# STM32F103RCT6_Core.net
KiCad netlist of a schematic drawn in Altium Designer
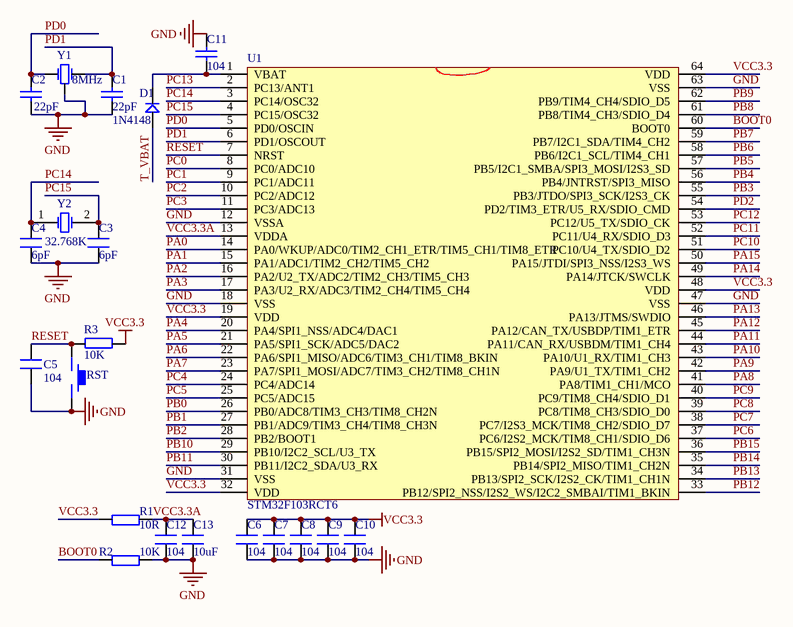
[diagram p0: STM32F103RCT6_Core.SchDoc]

(export (version "E")
  (design (tool "Eeschema 10.0.6"))
  (components
    (comp (ref "C1") (value "22pF") (footprint "C 0603_M") (libsource (lib "L476") (part "CAP")))
    (comp (ref "C2") (value "22pF") (footprint "C 0603_M") (libsource (lib "L476") (part "CAP")))
    (comp (ref "C3")
      (value "6pF")
      (footprint "C 0603_M")
      (libsource (lib "WarShip V3 STM32103封装库") (part "C"))
    )
    (comp (ref "C4")
      (value "6pF")
      (footprint "C 0603_M")
      (libsource (lib "WarShip V3 STM32103封装库") (part "C"))
    )
    (comp (ref "C5")
      (value "104")
      (footprint "C 0603_M")
      (libsource (lib "WarShip V3 STM32103封装库") (part "C"))
    )
    (comp (ref "C6")
      (value "104")
      (footprint "C 0603_M")
      (libsource (lib "WarShip V3 STM32103封装库") (part "C"))
    )
    (comp (ref "C7")
      (value "104")
      (footprint "C 0603_M")
      (libsource (lib "WarShip V3 STM32103封装库") (part "C"))
    )
    (comp (ref "C8")
      (value "104")
      (footprint "C 0603_M")
      (libsource (lib "WarShip V3 STM32103封装库") (part "C"))
    )
    (comp (ref "C9")
      (value "104")
      (footprint "C 0603_M")
      (libsource (lib "WarShip V3 STM32103封装库") (part "C"))
    )
    (comp (ref "C10")
      (value "104")
      (footprint "C 0603_M")
      (libsource (lib "WarShip V3 STM32103封装库") (part "C"))
    )
    (comp (ref "C11") (value "104") (footprint "C 0603_M") (libsource (lib "L476") (part "CAP")))
    (comp (ref "C12")
      (value "104")
      (footprint "C 0603_M")
      (libsource (lib "WarShip V3 STM32103封装库") (part "C"))
    )
    (comp (ref "C13")
      (value "10uF")
      (footprint "C 0603_M")
      (libsource (lib "WarShip V3 STM32103封装库") (part "C"))
    )
    (comp (ref "D1")
      (value "1N4148")
      (footprint "MINI_MELF (LL34)")
      (libsource (lib "阿波罗STM32F4&F7底板封装库") (part "D"))
    )
    (comp (ref "R1")
      (value "10R")
      (footprint "R 0603_M")
      (libsource (lib "WarShip V3 STM32103封装库") (part "R"))
    )
    (comp (ref "R2")
      (value "10K")
      (footprint "R 0603_M")
      (libsource (lib "WarShip V3 STM32103封装库") (part "R"))
    )
    (comp (ref "R3")
      (value "10K")
      (footprint "R 0603_M")
      (libsource (lib "WarShip V3 STM32103封装库") (part "R"))
    )
    (comp (ref "RST")
      (value "S-KEY-SMD-324225")
      (footprint "TSW SMD-3*6*2.5")
      (description "KEY,SMD,324225")
      (libsource (lib "Pandora_STM32L4_Board_V2.4") (part "S-KEY-SMD-324225"))
    )
    (comp (ref "U1")
      (value "STM32F103RCT6")
      (footprint "LQFP-64N")
      (libsource (lib "MiniSTM32 V3.0封装库") (part "STM32F103RDT6"))
    )
    (comp (ref "Y1")
      (value "8MHz")
      (footprint "Y-XTAL-3215-3P")
      (description "XTAL,3215,8MHz")
      (libsource (lib "Pandora_STM32L4_Board_V2.4") (part "Y-3215-8M"))
    )
    (comp (ref "Y2")
      (value "32.768K")
      (footprint "OSC 3215-2P")
      (description "Crystal Oscillator")
      (fields (field (name "PUBLISHER") "Altium Limited"))
      (libsource (lib "WarShip V3 STM32103封装库") (part "XTAL"))
    )
  )
  (nets
    (net (code "1") (name "/BOOT0") (class "Default")
      (node (ref "R2") (pin "1") (pintype "passive"))
      (node (ref "U1") (pin "60") (pinfunction "BOOT0_60") (pintype "passive"))
    )
    (net (code "2") (name "/PA0") (class "Default")
      (node (ref "U1") (pin "14") (pinfunction "PA0/WKUP/ADC0/TIM2_CH1_ETR/TIM5_CH1/TIM8_ETR_14") (pintype "passive"))
    )
    (net (code "3") (name "/PA1") (class "Default")
      (node (ref "U1") (pin "15") (pinfunction "PA1/ADC1/TIM2_CH2/TIM5_CH2_15") (pintype "passive"))
    )
    (net (code "4") (name "/PA2") (class "Default")
      (node (ref "U1") (pin "16") (pinfunction "PA2/U2_TX/ADC2/TIM2_CH3/TIM5_CH3_16") (pintype "passive"))
    )
    (net (code "5") (name "/PA3") (class "Default")
      (node (ref "U1") (pin "17") (pinfunction "PA3/U2_RX/ADC3/TIM2_CH4/TIM5_CH4_17") (pintype "passive"))
    )
    (net (code "6") (name "/PA4") (class "Default")
      (node (ref "U1") (pin "20") (pinfunction "PA4/SPI1_NSS/ADC4/DAC1_20") (pintype "passive"))
    )
    (net (code "7") (name "/PA5") (class "Default")
      (node (ref "U1") (pin "21") (pinfunction "PA5/SPI1_SCK/ADC5/DAC2_21") (pintype "passive"))
    )
    (net (code "8") (name "/PA6") (class "Default")
      (node (ref "U1") (pin "22") (pinfunction "PA6/SPI1_MISO/ADC6/TIM3_CH1/TIM8_BKIN_22") (pintype "passive"))
    )
    (net (code "9") (name "/PA7") (class "Default")
      (node (ref "U1") (pin "23") (pinfunction "PA7/SPI1_MOSI/ADC7/TIM3_CH2/TIM8_CH1N_23") (pintype "passive"))
    )
    (net (code "10") (name "/PA8") (class "Default")
      (node (ref "U1") (pin "41") (pinfunction "PA8/TIM1_CH1/MCO_41") (pintype "passive"))
    )
    (net (code "11") (name "/PA9") (class "Default")
      (node (ref "U1") (pin "42") (pinfunction "PA9/U1_TX/TIM1_CH2_42") (pintype "passive"))
    )
    (net (code "12") (name "/PA10") (class "Default")
      (node (ref "U1") (pin "43") (pinfunction "PA10/U1_RX/TIM1_CH3_43") (pintype "passive"))
    )
    (net (code "13") (name "/PA11") (class "Default")
      (node (ref "U1") (pin "44") (pinfunction "PA11/CAN_RX/USBDM/TIM1_CH4_44") (pintype "passive"))
    )
    (net (code "14") (name "/PA12") (class "Default")
      (node (ref "U1") (pin "45") (pinfunction "PA12/CAN_TX/USBDP/TIM1_ETR_45") (pintype "passive"))
    )
    (net (code "15") (name "/PA13") (class "Default")
      (node (ref "U1") (pin "46") (pinfunction "PA13/JTMS/SWDIO_46") (pintype "passive"))
    )
    (net (code "16") (name "/PA14") (class "Default")
      (node (ref "U1") (pin "49") (pinfunction "PA14/JTCK/SWCLK_49") (pintype "passive"))
    )
    (net (code "17") (name "/PA15") (class "Default")
      (node (ref "U1") (pin "50") (pinfunction "PA15/JTDI/SPI3_NSS/I2S3_WS_50") (pintype "passive"))
    )
    (net (code "18") (name "/PB0") (class "Default")
      (node (ref "U1") (pin "26") (pinfunction "PB0/ADC8/TIM3_CH3/TIM8_CH2N_26") (pintype "passive"))
    )
    (net (code "19") (name "/PB1") (class "Default")
      (node (ref "U1") (pin "27") (pinfunction "PB1/ADC9/TIM3_CH4/TIM8_CH3N_27") (pintype "passive"))
    )
    (net (code "20") (name "/PB2") (class "Default")
      (node (ref "U1") (pin "28") (pinfunction "PB2/BOOT1_28") (pintype "passive"))
    )
    (net (code "21") (name "/PB3") (class "Default")
      (node (ref "U1") (pin "55") (pinfunction "PB3/JTDO/SPI3_SCK/I2S3_CK_55") (pintype "passive"))
    )
    (net (code "22") (name "/PB4") (class "Default")
      (node (ref "U1") (pin "56") (pinfunction "PB4/JNTRST/SPI3_MISO_56") (pintype "passive"))
    )
    (net (code "23") (name "/PB5") (class "Default")
      (node (ref "U1") (pin "57") (pinfunction "PB5/I2C1_SMBA/SPI3_MOSI/I2S3_SD_57") (pintype "passive"))
    )
    (net (code "24") (name "/PB6") (class "Default")
      (node (ref "U1") (pin "58") (pinfunction "PB6/I2C1_SCL/TIM4_CH1_58") (pintype "passive"))
    )
    (net (code "25") (name "/PB7") (class "Default")
      (node (ref "U1") (pin "59") (pinfunction "PB7/I2C1_SDA/TIM4_CH2_59") (pintype "passive"))
    )
    (net (code "26") (name "/PB8") (class "Default")
      (node (ref "U1") (pin "61") (pinfunction "PB8/TIM4_CH3/SDIO_D4_61") (pintype "passive"))
    )
    (net (code "27") (name "/PB9") (class "Default")
      (node (ref "U1") (pin "62") (pinfunction "PB9/TIM4_CH4/SDIO_D5_62") (pintype "passive"))
    )
    (net (code "28") (name "/PB10") (class "Default")
      (node (ref "U1") (pin "29") (pinfunction "PB10/I2C2_SCL/U3_TX_29") (pintype "passive"))
    )
    (net (code "29") (name "/PB11") (class "Default")
      (node (ref "U1") (pin "30") (pinfunction "PB11/I2C2_SDA/U3_RX_30") (pintype "passive"))
    )
    (net (code "30") (name "/PB12") (class "Default")
      (node (ref "U1") (pin "33") (pinfunction "PB12/SPI2_NSS/I2S2_WS/I2C2_SMBAI/TIM1_BKIN_33") (pintype "passive"))
    )
    (net (code "31") (name "/PB13") (class "Default")
      (node (ref "U1") (pin "34") (pinfunction "PB13/SPI2_SCK/I2S2_CK/TIM1_CH1N_34") (pintype "passive"))
    )
    (net (code "32") (name "/PB14") (class "Default")
      (node (ref "U1") (pin "35") (pinfunction "PB14/SPI2_MISO/TIM1_CH2N_35") (pintype "passive"))
    )
    (net (code "33") (name "/PB15") (class "Default")
      (node (ref "U1") (pin "36") (pinfunction "PB15/SPI2_MOSI/I2S2_SD/TIM1_CH3N_36") (pintype "passive"))
    )
    (net (code "34") (name "/PC0") (class "Default")
      (node (ref "U1") (pin "8") (pinfunction "PC0/ADC10_8") (pintype "passive"))
    )
    (net (code "35") (name "/PC1") (class "Default")
      (node (ref "U1") (pin "9") (pinfunction "PC1/ADC11_9") (pintype "passive"))
    )
    (net (code "36") (name "/PC2") (class "Default")
      (node (ref "U1") (pin "10") (pinfunction "PC2/ADC12_10") (pintype "passive"))
    )
    (net (code "37") (name "/PC3") (class "Default")
      (node (ref "U1") (pin "11") (pinfunction "PC3/ADC13_11") (pintype "passive"))
    )
    (net (code "38") (name "/PC4") (class "Default")
      (node (ref "U1") (pin "24") (pinfunction "PC4/ADC14_24") (pintype "passive"))
    )
    (net (code "39") (name "/PC5") (class "Default")
      (node (ref "U1") (pin "25") (pinfunction "PC5/ADC15_25") (pintype "passive"))
    )
    (net (code "40") (name "/PC6") (class "Default")
      (node (ref "U1") (pin "37") (pinfunction "PC6/I2S2_MCK/TIM8_CH1/SDIO_D6_37") (pintype "passive"))
    )
    (net (code "41") (name "/PC7") (class "Default")
      (node (ref "U1") (pin "38") (pinfunction "PC7/I2S3_MCK/TIM8_CH2/SDIO_D7_38") (pintype "passive"))
    )
    (net (code "42") (name "/PC8") (class "Default")
      (node (ref "U1") (pin "39") (pinfunction "PC8/TIM8_CH3/SDIO_D0_39") (pintype "passive"))
    )
    (net (code "43") (name "/PC9") (class "Default")
      (node (ref "U1") (pin "40") (pinfunction "PC9/TIM8_CH4/SDIO_D1_40") (pintype "passive"))
    )
    (net (code "44") (name "/PC10") (class "Default")
      (node (ref "U1") (pin "51") (pinfunction "PC10/U4_TX/SDIO_D2_51") (pintype "passive"))
    )
    (net (code "45") (name "/PC11") (class "Default")
      (node (ref "U1") (pin "52") (pinfunction "PC11/U4_RX/SDIO_D3_52") (pintype "passive"))
    )
    (net (code "46") (name "/PC12") (class "Default")
      (node (ref "U1") (pin "53") (pinfunction "PC12/U5_TX/SDIO_CK_53") (pintype "passive"))
    )
    (net (code "47") (name "/PC13") (class "Default")
      (node (ref "U1") (pin "2") (pinfunction "PC13/ANT1_2") (pintype "passive"))
    )
    (net (code "48") (name "/PC14") (class "Default")
      (node (ref "C4") (pin "2") (pintype "passive"))
      (node (ref "U1") (pin "3") (pinfunction "PC14/OSC32_3") (pintype "passive"))
      (node (ref "Y2") (pin "1") (pinfunction "OSC1_1") (pintype "passive"))
    )
    (net (code "49") (name "/PC15") (class "Default")
      (node (ref "C3") (pin "2") (pintype "passive"))
      (node (ref "U1") (pin "4") (pinfunction "PC15/OSC32_4") (pintype "passive"))
      (node (ref "Y2") (pin "2") (pinfunction "OSC2_2") (pintype "passive"))
    )
    (net (code "50") (name "/PD0") (class "Default")
      (node (ref "C2") (pin "2") (pinfunction "2_2") (pintype "passive"))
      (node (ref "U1") (pin "5") (pinfunction "PD0/OSCIN_5") (pintype "passive"))
      (node (ref "Y1") (pin "1") (pinfunction "OSC1_1") (pintype "passive"))
    )
    (net (code "51") (name "/PD1") (class "Default")
      (node (ref "C1") (pin "2") (pinfunction "2_2") (pintype "passive"))
      (node (ref "U1") (pin "6") (pinfunction "PD1/OSCOUT_6") (pintype "passive"))
      (node (ref "Y1") (pin "3") (pinfunction "OSC2_3") (pintype "passive"))
    )
    (net (code "52") (name "/PD2") (class "Default")
      (node (ref "U1") (pin "54") (pinfunction "PD2/TIM3_ETR/U5_RX/SDIO_CMD_54") (pintype "passive"))
    )
    (net (code "53") (name "/RESET") (class "Default")
      (node (ref "C5") (pin "2") (pintype "passive"))
      (node (ref "R3") (pin "2") (pintype "passive"))
      (node (ref "RST") (pin "1") (pinfunction "1_1") (pintype "passive"))
      (node (ref "U1") (pin "7") (pinfunction "NRST_7") (pintype "passive"))
    )
    (net (code "54") (name "/T_VBAT") (class "Default") (node (ref "D1") (pin "1") (pintype "passive")))
    (net (code "55") (name "/VCC3.3A") (class "Default")
      (node (ref "C12") (pin "2") (pintype "passive"))
      (node (ref "C13") (pin "2") (pintype "passive"))
      (node (ref "R1") (pin "2") (pintype "passive"))
      (node (ref "U1") (pin "13") (pinfunction "VDDA_13") (pintype "passive"))
    )
    (net (code "56") (name "GND") (class "Default")
      (node (ref "C1") (pin "1") (pinfunction "1_1") (pintype "passive"))
      (node (ref "C10") (pin "1") (pintype "passive"))
      (node (ref "C11") (pin "1") (pinfunction "1_1") (pintype "passive"))
      (node (ref "C12") (pin "1") (pintype "passive"))
      (node (ref "C13") (pin "1") (pintype "passive"))
      (node (ref "C2") (pin "1") (pinfunction "1_1") (pintype "passive"))
      (node (ref "C3") (pin "1") (pintype "passive"))
      (node (ref "C4") (pin "1") (pintype "passive"))
      (node (ref "C5") (pin "1") (pintype "passive"))
      (node (ref "C6") (pin "1") (pintype "passive"))
      (node (ref "C7") (pin "1") (pintype "passive"))
      (node (ref "C8") (pin "1") (pintype "passive"))
      (node (ref "C9") (pin "1") (pintype "passive"))
      (node (ref "R2") (pin "2") (pintype "passive"))
      (node (ref "RST") (pin "2") (pinfunction "2_2") (pintype "passive"))
      (node (ref "U1") (pin "12") (pinfunction "VSSA_12") (pintype "passive"))
      (node (ref "U1") (pin "18") (pinfunction "VSS_18") (pintype "passive"))
      (node (ref "U1") (pin "31") (pinfunction "VSS_31") (pintype "passive"))
      (node (ref "U1") (pin "47") (pinfunction "VSS_47") (pintype "passive"))
      (node (ref "U1") (pin "63") (pinfunction "VSS_63") (pintype "passive"))
      (node (ref "Y1") (pin "2") (pinfunction "GND_2") (pintype "passive"))
    )
    (net (code "57") (name "Net-(U1-VBAT)") (class "Default")
      (node (ref "C11") (pin "2") (pinfunction "2_2") (pintype "passive"))
      (node (ref "D1") (pin "2") (pintype "passive"))
      (node (ref "U1") (pin "1") (pinfunction "VBAT_1") (pintype "passive"))
    )
    (net (code "58") (name "VCC3.3") (class "Default")
      (node (ref "C10") (pin "2") (pintype "passive"))
      (node (ref "C6") (pin "2") (pintype "passive"))
      (node (ref "C7") (pin "2") (pintype "passive"))
      (node (ref "C8") (pin "2") (pintype "passive"))
      (node (ref "C9") (pin "2") (pintype "passive"))
      (node (ref "R1") (pin "1") (pintype "passive"))
      (node (ref "R3") (pin "1") (pintype "passive"))
      (node (ref "U1") (pin "19") (pinfunction "VDD_19") (pintype "passive"))
      (node (ref "U1") (pin "32") (pinfunction "VDD_32") (pintype "passive"))
      (node (ref "U1") (pin "48") (pinfunction "VDD_48") (pintype "passive"))
      (node (ref "U1") (pin "64") (pinfunction "VDD_64") (pintype "passive"))
    )
  )
)
